# design.net
KiCad netlist of a schematic drawn in Altium Designer
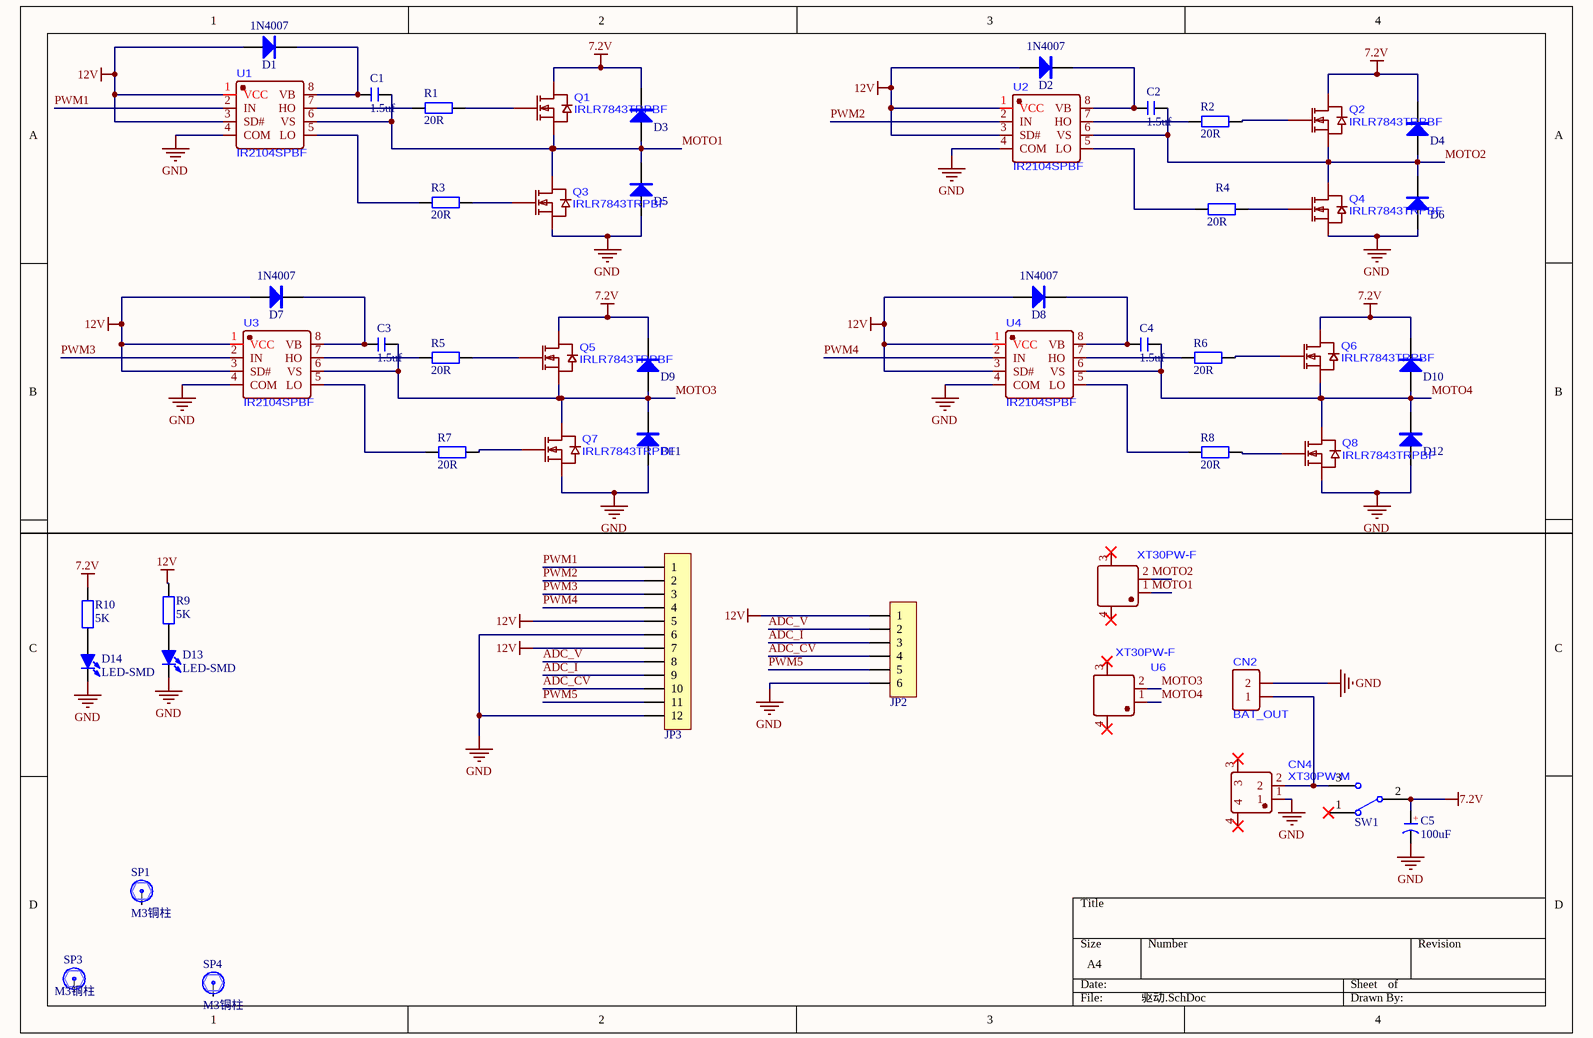
[diagram p0: 驱动.SchDoc]

(export (version "E")
  (design (tool "Eeschema 10.0.6"))
  (components
    (comp (ref "C1")
      (value "1.5uf")
      (footprint "C 0603_M")
      (description "无极性贴片电容")
      (fields (field (name "版权归属") "源创客"))
      (libsource (lib "电阻-电容-电感") (part "C"))
    )
    (comp (ref "C2")
      (value "1.5uf")
      (footprint "C 0603_M")
      (description "无极性贴片电容")
      (fields (field (name "版权归属") "源创客"))
      (libsource (lib "电阻-电容-电感") (part "C"))
    )
    (comp (ref "C3")
      (value "1.5uf")
      (footprint "C 0603_M")
      (description "无极性贴片电容")
      (fields (field (name "版权归属") "源创客"))
      (libsource (lib "电阻-电容-电感") (part "C"))
    )
    (comp (ref "C4")
      (value "1.5uf")
      (footprint "C 0603_M")
      (description "无极性贴片电容")
      (fields (field (name "版权归属") "源创客"))
      (libsource (lib "电阻-电容-电感") (part "C"))
    )
    (comp (ref "C5")
      (value "100uF")
      (footprint "CAP 2.0*5*11-H - BK")
      (description "直插电解电容")
      (fields (field (name "Comment") "C-CAP") (field (name "版权归属") "电协硬件组"))
      (libsource (lib "3.1   - 电阻-电容-电感") (part "C-CAP"))
    )
    (comp (ref "CN2")
      (value "BAT_OUT")
      (footprint "CONN-TH_XT30UPB-F")
      (libsource (lib "驱动") (part "XT30UPB-F"))
    )
    (comp (ref "CN4")
      (value "XT30PW-M")
      (footprint "CONN-TH_XT30PW-M")
      (libsource (lib "主控") (part "XT30PW-M"))
    )
    (comp (ref "D1")
      (value "1N4007")
      (footprint "SMA")
      (description "肖特基二极管")
      (fields (field (name "版权归属") "电协硬件组"))
      (libsource (lib "8.1   - 二极管-整流桥") (part "SS14"))
    )
    (comp (ref "D2")
      (value "1N4007")
      (footprint "SMA")
      (description "肖特基二极管")
      (fields (field (name "版权归属") "电协硬件组"))
      (libsource (lib "8.1   - 二极管-整流桥") (part "SS14"))
    )
    (comp (ref "D3")
      (value "SS14")
      (footprint "SMA")
      (description "肖特基二极管")
      (fields (field (name "版权归属") "电协硬件组"))
      (libsource (lib "8.1   - 二极管-整流桥") (part "SS14"))
    )
    (comp (ref "D4")
      (value "SS14")
      (footprint "SMA")
      (description "肖特基二极管")
      (fields (field (name "版权归属") "电协硬件组"))
      (libsource (lib "8.1   - 二极管-整流桥") (part "SS14"))
    )
    (comp (ref "D5")
      (value "SS14")
      (footprint "SMA")
      (description "肖特基二极管")
      (fields (field (name "版权归属") "电协硬件组"))
      (libsource (lib "8.1   - 二极管-整流桥") (part "SS14"))
    )
    (comp (ref "D6")
      (value "SS14")
      (footprint "SMA")
      (description "肖特基二极管")
      (fields (field (name "版权归属") "电协硬件组"))
      (libsource (lib "8.1   - 二极管-整流桥") (part "SS14"))
    )
    (comp (ref "D7")
      (value "1N4007")
      (footprint "SMA")
      (description "肖特基二极管")
      (fields (field (name "版权归属") "电协硬件组"))
      (libsource (lib "8.1   - 二极管-整流桥") (part "SS14"))
    )
    (comp (ref "D8")
      (value "1N4007")
      (footprint "SMA")
      (description "肖特基二极管")
      (fields (field (name "版权归属") "电协硬件组"))
      (libsource (lib "8.1   - 二极管-整流桥") (part "SS14"))
    )
    (comp (ref "D9")
      (value "SS14")
      (footprint "SMA")
      (description "肖特基二极管")
      (fields (field (name "版权归属") "电协硬件组"))
      (libsource (lib "8.1   - 二极管-整流桥") (part "SS14"))
    )
    (comp (ref "D10")
      (value "SS14")
      (footprint "SMA")
      (description "肖特基二极管")
      (fields (field (name "版权归属") "电协硬件组"))
      (libsource (lib "8.1   - 二极管-整流桥") (part "SS14"))
    )
    (comp (ref "D11")
      (value "SS14")
      (footprint "SMA")
      (description "肖特基二极管")
      (fields (field (name "版权归属") "电协硬件组"))
      (libsource (lib "8.1   - 二极管-整流桥") (part "SS14"))
    )
    (comp (ref "D12")
      (value "SS14")
      (footprint "SMA")
      (description "肖特基二极管")
      (fields (field (name "版权归属") "电协硬件组"))
      (libsource (lib "8.1   - 二极管-整流桥") (part "SS14"))
    )
    (comp (ref "D13")
      (value "LED-SMD")
      (footprint "LED 0603G")
      (description "贴片LED")
      (fields (field (name "版权归属") "电协硬件组"))
      (libsource (lib "9.1   - LED") (part "LED-SMD"))
    )
    (comp (ref "D14")
      (value "LED-SMD")
      (footprint "LED 0603G")
      (description "贴片LED")
      (fields (field (name "版权归属") "电协硬件组"))
      (libsource (lib "9.1   - LED") (part "LED-SMD"))
    )
    (comp (ref "JP2")
      (value "HDR-1X6")
      (footprint "XH2.54-WI-6P")
      (description "6P接插件")
      (fields (field (name "版权归属") "源创客"))
      (libsource (lib "4.5   - 接插件-脚距2.54") (part "Header 6"))
    )
    (comp (ref "JP3")
      (value "HDR-1X12")
      (footprint "XH2.54-WI-12P")
      (description "12P接插件")
      (fields (field (name "版权归属") "源创客"))
      (libsource (lib "4.5   - 接插件-脚距2.54") (part "Header 12"))
    )
    (comp (ref "Q1")
      (value "IRLR7843TRPBF")
      (footprint "TO-252-2_L6.5-W6.1-P4.58-LS10.0-TR")
      (libsource (lib "驱动") (part "IRLR7843TRPBF"))
    )
    (comp (ref "Q2")
      (value "IRLR7843TRPBF")
      (footprint "TO-252-2_L6.5-W6.1-P4.58-LS10.0-TR")
      (libsource (lib "驱动") (part "IRLR7843TRPBF"))
    )
    (comp (ref "Q3")
      (value "IRLR7843TRPBF")
      (footprint "TO-252-2_L6.5-W6.1-P4.58-LS10.0-TR")
      (libsource (lib "驱动") (part "IRLR7843TRPBF"))
    )
    (comp (ref "Q4")
      (value "IRLR7843TRPBF")
      (footprint "TO-252-2_L6.5-W6.1-P4.58-LS10.0-TR")
      (libsource (lib "驱动") (part "IRLR7843TRPBF"))
    )
    (comp (ref "Q5")
      (value "IRLR7843TRPBF")
      (footprint "TO-252-2_L6.5-W6.1-P4.58-LS10.0-TR")
      (libsource (lib "驱动") (part "IRLR7843TRPBF"))
    )
    (comp (ref "Q6")
      (value "IRLR7843TRPBF")
      (footprint "TO-252-2_L6.5-W6.1-P4.58-LS10.0-TR")
      (libsource (lib "驱动") (part "IRLR7843TRPBF"))
    )
    (comp (ref "Q7")
      (value "IRLR7843TRPBF")
      (footprint "TO-252-2_L6.5-W6.1-P4.58-LS10.0-TR")
      (libsource (lib "驱动") (part "IRLR7843TRPBF"))
    )
    (comp (ref "Q8")
      (value "IRLR7843TRPBF")
      (footprint "TO-252-2_L6.5-W6.1-P4.58-LS10.0-TR")
      (libsource (lib "驱动") (part "IRLR7843TRPBF"))
    )
    (comp (ref "R1")
      (value "20R")
      (footprint "C 0603_M")
      (description "贴片电阻")
      (fields (field (name "版权归属") "源创客"))
      (libsource (lib "电阻-电容-电感") (part "R"))
    )
    (comp (ref "R2")
      (value "20R")
      (footprint "C 0603_M")
      (description "贴片电阻")
      (fields (field (name "版权归属") "源创客"))
      (libsource (lib "电阻-电容-电感") (part "R"))
    )
    (comp (ref "R3")
      (value "20R")
      (footprint "C 0603_M")
      (description "贴片电阻")
      (fields (field (name "版权归属") "源创客"))
      (libsource (lib "电阻-电容-电感") (part "R"))
    )
    (comp (ref "R4")
      (value "20R")
      (footprint "C 0603_M")
      (description "贴片电阻")
      (fields (field (name "版权归属") "源创客"))
      (libsource (lib "电阻-电容-电感") (part "R"))
    )
    (comp (ref "R5")
      (value "20R")
      (footprint "C 0603_M")
      (description "贴片电阻")
      (fields (field (name "版权归属") "源创客"))
      (libsource (lib "电阻-电容-电感") (part "R"))
    )
    (comp (ref "R6")
      (value "20R")
      (footprint "C 0603_M")
      (description "贴片电阻")
      (fields (field (name "版权归属") "源创客"))
      (libsource (lib "电阻-电容-电感") (part "R"))
    )
    (comp (ref "R7")
      (value "20R")
      (footprint "C 0603_M")
      (description "贴片电阻")
      (fields (field (name "版权归属") "源创客"))
      (libsource (lib "电阻-电容-电感") (part "R"))
    )
    (comp (ref "R8")
      (value "20R")
      (footprint "C 0603_M")
      (description "贴片电阻")
      (fields (field (name "版权归属") "源创客"))
      (libsource (lib "电阻-电容-电感") (part "R"))
    )
    (comp (ref "R9")
      (value "5K")
      (footprint "R 0603_M")
      (description "贴片电阻")
      (fields (field (name "Comment") "R") (field (name "版权归属") "电协硬件组"))
      (libsource (lib "3.1   - 电阻-电容-电感") (part "R"))
    )
    (comp (ref "R10")
      (value "5K")
      (footprint "R 0603_M")
      (description "贴片电阻")
      (fields (field (name "Comment") "R") (field (name "版权归属") "电协硬件组"))
      (libsource (lib "3.1   - 电阻-电容-电感") (part "R"))
    )
    (comp (ref "SP1")
      (value "M3铜柱")
      (footprint "M3x4+6_L")
      (description "铜柱")
      (fields (field (name "版权归属") "电协硬件组"))
      (libsource (lib "15.1 - 未分类器件") (part "铜柱加头小焊盘"))
    )
    (comp (ref "SP3")
      (value "M3铜柱")
      (footprint "M3x4+6_L")
      (description "铜柱")
      (fields (field (name "版权归属") "电协硬件组"))
      (libsource (lib "15.1 - 未分类器件") (part "铜柱加头小焊盘"))
    )
    (comp (ref "SP4")
      (value "M3铜柱")
      (footprint "M3x4+6_L")
      (description "铜柱")
      (fields (field (name "版权归属") "电协硬件组"))
      (libsource (lib "15.1 - 未分类器件") (part "铜柱加头小焊盘"))
    )
    (comp (ref "SW1")
      (value "MTS-10x")
      (footprint "MTS-10x")
      (description "MTS10x系列3脚扭子开关")
      (fields (field (name "版权归属") "电协硬件组"))
      (libsource (lib "5.1   - 按键-开关") (part "MTS-10x"))
    )
    (comp (ref "U1")
      (value "IR2104SPBF")
      (footprint "SOIC-8_L5.0-W4.0-P1.27-LS6.0-BL")
      (libsource (lib "驱动") (part "IR2104SPBF"))
    )
    (comp (ref "U2")
      (value "IR2104SPBF")
      (footprint "SOIC-8_L5.0-W4.0-P1.27-LS6.0-BL")
      (libsource (lib "驱动") (part "IR2104SPBF"))
    )
    (comp (ref "U3")
      (value "IR2104SPBF")
      (footprint "SOIC-8_L5.0-W4.0-P1.27-LS6.0-BL")
      (libsource (lib "驱动") (part "IR2104SPBF"))
    )
    (comp (ref "U4")
      (value "IR2104SPBF")
      (footprint "SOIC-8_L5.0-W4.0-P1.27-LS6.0-BL")
      (libsource (lib "驱动") (part "IR2104SPBF"))
    )
    (comp (ref "U5")
      (value "XT30PW-F")
      (footprint "CONN-TH_XT30PW-F")
      (libsource (lib "主控") (part "XT30PW-F"))
    )
    (comp (ref "U6")
      (value "XT30PW-F")
      (footprint "CONN-TH_XT30PW-F")
      (libsource (lib "主控") (part "XT30PW-F"))
    )
  )
  (nets
    (net (code "1") (name "/ADC_CV") (class "Default")
      (node (ref "JP2") (pin "4") (pinfunction "4_4") (pintype "passive"))
      (node (ref "JP3") (pin "10") (pinfunction "10_10") (pintype "passive"))
    )
    (net (code "2") (name "/ADC_I") (class "Default")
      (node (ref "JP2") (pin "3") (pinfunction "3_3") (pintype "passive"))
      (node (ref "JP3") (pin "9") (pinfunction "9_9") (pintype "passive"))
    )
    (net (code "3") (name "/ADC_V") (class "Default")
      (node (ref "JP2") (pin "2") (pinfunction "2_2") (pintype "passive"))
      (node (ref "JP3") (pin "8") (pinfunction "8_8") (pintype "passive"))
    )
    (net (code "4") (name "/MOTO1") (class "Default")
      (node (ref "C1") (pin "2") (pinfunction "2_2") (pintype "passive"))
      (node (ref "D3") (pin "1") (pinfunction "A_1") (pintype "passive"))
      (node (ref "D5") (pin "2") (pinfunction "K_2") (pintype "passive"))
      (node (ref "Q1") (pin "3") (pinfunction "S_3") (pintype "passive"))
      (node (ref "Q3") (pin "4") (pinfunction "D_4") (pintype "passive"))
      (node (ref "U1") (pin "6") (pinfunction "VS_6") (pintype "passive"))
      (node (ref "U5") (pin "1") (pinfunction "1_1") (pintype "passive"))
    )
    (net (code "5") (name "/MOTO2") (class "Default")
      (node (ref "C2") (pin "2") (pinfunction "2_2") (pintype "passive"))
      (node (ref "D4") (pin "1") (pinfunction "A_1") (pintype "passive"))
      (node (ref "D6") (pin "2") (pinfunction "K_2") (pintype "passive"))
      (node (ref "Q2") (pin "3") (pinfunction "S_3") (pintype "passive"))
      (node (ref "Q4") (pin "4") (pinfunction "D_4") (pintype "passive"))
      (node (ref "U2") (pin "6") (pinfunction "VS_6") (pintype "passive"))
      (node (ref "U5") (pin "2") (pinfunction "2_2") (pintype "passive"))
    )
    (net (code "6") (name "/MOTO3") (class "Default")
      (node (ref "C3") (pin "2") (pinfunction "2_2") (pintype "passive"))
      (node (ref "D11") (pin "2") (pinfunction "K_2") (pintype "passive"))
      (node (ref "D9") (pin "1") (pinfunction "A_1") (pintype "passive"))
      (node (ref "Q5") (pin "3") (pinfunction "S_3") (pintype "passive"))
      (node (ref "Q7") (pin "4") (pinfunction "D_4") (pintype "passive"))
      (node (ref "U3") (pin "6") (pinfunction "VS_6") (pintype "passive"))
      (node (ref "U6") (pin "2") (pinfunction "2_2") (pintype "passive"))
    )
    (net (code "7") (name "/MOTO4") (class "Default")
      (node (ref "C4") (pin "2") (pinfunction "2_2") (pintype "passive"))
      (node (ref "D10") (pin "1") (pinfunction "A_1") (pintype "passive"))
      (node (ref "D12") (pin "2") (pinfunction "K_2") (pintype "passive"))
      (node (ref "Q6") (pin "3") (pinfunction "S_3") (pintype "passive"))
      (node (ref "Q8") (pin "4") (pinfunction "D_4") (pintype "passive"))
      (node (ref "U4") (pin "6") (pinfunction "VS_6") (pintype "passive"))
      (node (ref "U6") (pin "1") (pinfunction "1_1") (pintype "passive"))
    )
    (net (code "8") (name "/PWM1") (class "Default")
      (node (ref "JP3") (pin "1") (pinfunction "1_1") (pintype "passive"))
      (node (ref "U1") (pin "2") (pinfunction "IN_2") (pintype "passive"))
    )
    (net (code "9") (name "/PWM2") (class "Default")
      (node (ref "JP3") (pin "2") (pinfunction "2_2") (pintype "passive"))
      (node (ref "U2") (pin "2") (pinfunction "IN_2") (pintype "passive"))
    )
    (net (code "10") (name "/PWM3") (class "Default")
      (node (ref "JP3") (pin "3") (pinfunction "3_3") (pintype "passive"))
      (node (ref "U3") (pin "2") (pinfunction "IN_2") (pintype "passive"))
    )
    (net (code "11") (name "/PWM4") (class "Default")
      (node (ref "JP3") (pin "4") (pinfunction "4_4") (pintype "passive"))
      (node (ref "U4") (pin "2") (pinfunction "IN_2") (pintype "passive"))
    )
    (net (code "12") (name "/PWM5") (class "Default")
      (node (ref "JP2") (pin "5") (pinfunction "5_5") (pintype "passive"))
      (node (ref "JP3") (pin "11") (pinfunction "11_11") (pintype "passive"))
    )
    (net (code "13") (name "7.2V") (class "Default")
      (node (ref "C5") (pin "1") (pinfunction "A_1") (pintype "passive"))
      (node (ref "D10") (pin "2") (pinfunction "K_2") (pintype "passive"))
      (node (ref "D3") (pin "2") (pinfunction "K_2") (pintype "passive"))
      (node (ref "D4") (pin "2") (pinfunction "K_2") (pintype "passive"))
      (node (ref "D9") (pin "2") (pinfunction "K_2") (pintype "passive"))
      (node (ref "Q1") (pin "4") (pinfunction "D_4") (pintype "passive"))
      (node (ref "Q2") (pin "4") (pinfunction "D_4") (pintype "passive"))
      (node (ref "Q5") (pin "4") (pinfunction "D_4") (pintype "passive"))
      (node (ref "Q6") (pin "4") (pinfunction "D_4") (pintype "passive"))
      (node (ref "R10") (pin "1") (pinfunction "1_1") (pintype "passive"))
      (node (ref "SW1") (pin "2") (pinfunction "2_2") (pintype "passive"))
    )
    (net (code "14") (name "12V") (class "Default")
      (node (ref "D1") (pin "1") (pinfunction "A_1") (pintype "passive"))
      (node (ref "D2") (pin "1") (pinfunction "A_1") (pintype "passive"))
      (node (ref "D7") (pin "1") (pinfunction "A_1") (pintype "passive"))
      (node (ref "D8") (pin "1") (pinfunction "A_1") (pintype "passive"))
      (node (ref "JP2") (pin "1") (pinfunction "1_1") (pintype "passive"))
      (node (ref "JP3") (pin "5") (pinfunction "5_5") (pintype "passive"))
      (node (ref "JP3") (pin "7") (pinfunction "7_7") (pintype "passive"))
      (node (ref "R9") (pin "1") (pinfunction "1_1") (pintype "passive"))
      (node (ref "U1") (pin "1") (pinfunction "VCC_1") (pintype "passive"))
      (node (ref "U1") (pin "3") (pinfunction "SD#_3") (pintype "passive"))
      (node (ref "U2") (pin "1") (pinfunction "VCC_1") (pintype "passive"))
      (node (ref "U2") (pin "3") (pinfunction "SD#_3") (pintype "passive"))
      (node (ref "U3") (pin "1") (pinfunction "VCC_1") (pintype "passive"))
      (node (ref "U3") (pin "3") (pinfunction "SD#_3") (pintype "passive"))
      (node (ref "U4") (pin "1") (pinfunction "VCC_1") (pintype "passive"))
      (node (ref "U4") (pin "3") (pinfunction "SD#_3") (pintype "passive"))
    )
    (net (code "15") (name "GND") (class "Default")
      (node (ref "C5") (pin "2") (pinfunction "K_2") (pintype "passive"))
      (node (ref "CN2") (pin "2") (pinfunction "2_2") (pintype "passive"))
      (node (ref "CN4") (pin "1") (pinfunction "1_1") (pintype "passive"))
      (node (ref "D11") (pin "1") (pinfunction "A_1") (pintype "passive"))
      (node (ref "D12") (pin "1") (pinfunction "A_1") (pintype "passive"))
      (node (ref "D13") (pin "2") (pinfunction "K_2") (pintype "passive"))
      (node (ref "D14") (pin "2") (pinfunction "K_2") (pintype "passive"))
      (node (ref "D5") (pin "1") (pinfunction "A_1") (pintype "passive"))
      (node (ref "D6") (pin "1") (pinfunction "A_1") (pintype "passive"))
      (node (ref "JP2") (pin "6") (pinfunction "6_6") (pintype "passive"))
      (node (ref "JP3") (pin "12") (pinfunction "12_12") (pintype "passive"))
      (node (ref "JP3") (pin "6") (pinfunction "6_6") (pintype "passive"))
      (node (ref "Q3") (pin "3") (pinfunction "S_3") (pintype "passive"))
      (node (ref "Q4") (pin "3") (pinfunction "S_3") (pintype "passive"))
      (node (ref "Q7") (pin "3") (pinfunction "S_3") (pintype "passive"))
      (node (ref "Q8") (pin "3") (pinfunction "S_3") (pintype "passive"))
      (node (ref "U1") (pin "4") (pinfunction "COM_4") (pintype "passive"))
      (node (ref "U2") (pin "4") (pinfunction "COM_4") (pintype "passive"))
      (node (ref "U3") (pin "4") (pinfunction "COM_4") (pintype "passive"))
      (node (ref "U4") (pin "4") (pinfunction "COM_4") (pintype "passive"))
    )
    (net (code "16") (name "Net-(CN2-Pad1)") (class "Default")
      (node (ref "CN2") (pin "1") (pinfunction "1_1") (pintype "passive"))
      (node (ref "CN4") (pin "2") (pinfunction "2_2") (pintype "passive"))
      (node (ref "SW1") (pin "3") (pinfunction "3_3") (pintype "passive"))
    )
    (net (code "17") (name "Net-(D1-K)") (class "Default")
      (node (ref "C1") (pin "1") (pinfunction "1_1") (pintype "passive"))
      (node (ref "D1") (pin "2") (pinfunction "K_2") (pintype "passive"))
      (node (ref "U1") (pin "8") (pinfunction "VB_8") (pintype "passive"))
    )
    (net (code "18") (name "Net-(D2-K)") (class "Default")
      (node (ref "C2") (pin "1") (pinfunction "1_1") (pintype "passive"))
      (node (ref "D2") (pin "2") (pinfunction "K_2") (pintype "passive"))
      (node (ref "U2") (pin "8") (pinfunction "VB_8") (pintype "passive"))
    )
    (net (code "19") (name "Net-(D7-K)") (class "Default")
      (node (ref "C3") (pin "1") (pinfunction "1_1") (pintype "passive"))
      (node (ref "D7") (pin "2") (pinfunction "K_2") (pintype "passive"))
      (node (ref "U3") (pin "8") (pinfunction "VB_8") (pintype "passive"))
    )
    (net (code "20") (name "Net-(D8-K)") (class "Default")
      (node (ref "C4") (pin "1") (pinfunction "1_1") (pintype "passive"))
      (node (ref "D8") (pin "2") (pinfunction "K_2") (pintype "passive"))
      (node (ref "U4") (pin "8") (pinfunction "VB_8") (pintype "passive"))
    )
    (net (code "21") (name "Net-(D13-A)") (class "Default")
      (node (ref "D13") (pin "1") (pinfunction "A_1") (pintype "passive"))
      (node (ref "R9") (pin "2") (pinfunction "2_2") (pintype "passive"))
    )
    (net (code "22") (name "Net-(D14-A)") (class "Default")
      (node (ref "D14") (pin "1") (pinfunction "A_1") (pintype "passive"))
      (node (ref "R10") (pin "2") (pinfunction "2_2") (pintype "passive"))
    )
    (net (code "23") (name "Net-(Q1-G)") (class "Default")
      (node (ref "Q1") (pin "1") (pinfunction "G_1") (pintype "passive"))
      (node (ref "R1") (pin "2") (pinfunction "2_2") (pintype "passive"))
    )
    (net (code "24") (name "Net-(Q2-G)") (class "Default")
      (node (ref "Q2") (pin "1") (pinfunction "G_1") (pintype "passive"))
      (node (ref "R2") (pin "2") (pinfunction "2_2") (pintype "passive"))
    )
    (net (code "25") (name "Net-(Q3-G)") (class "Default")
      (node (ref "Q3") (pin "1") (pinfunction "G_1") (pintype "passive"))
      (node (ref "R3") (pin "2") (pinfunction "2_2") (pintype "passive"))
    )
    (net (code "26") (name "Net-(Q4-G)") (class "Default")
      (node (ref "Q4") (pin "1") (pinfunction "G_1") (pintype "passive"))
      (node (ref "R4") (pin "2") (pinfunction "2_2") (pintype "passive"))
    )
    (net (code "27") (name "Net-(Q5-G)") (class "Default")
      (node (ref "Q5") (pin "1") (pinfunction "G_1") (pintype "passive"))
      (node (ref "R5") (pin "2") (pinfunction "2_2") (pintype "passive"))
    )
    (net (code "28") (name "Net-(Q6-G)") (class "Default")
      (node (ref "Q6") (pin "1") (pinfunction "G_1") (pintype "passive"))
      (node (ref "R6") (pin "2") (pinfunction "2_2") (pintype "passive"))
    )
    (net (code "29") (name "Net-(Q7-G)") (class "Default")
      (node (ref "Q7") (pin "1") (pinfunction "G_1") (pintype "passive"))
      (node (ref "R7") (pin "2") (pinfunction "2_2") (pintype "passive"))
    )
    (net (code "30") (name "Net-(Q8-G)") (class "Default")
      (node (ref "Q8") (pin "1") (pinfunction "G_1") (pintype "passive"))
      (node (ref "R8") (pin "2") (pinfunction "2_2") (pintype "passive"))
    )
    (net (code "31") (name "Net-(U1-HO)") (class "Default")
      (node (ref "R1") (pin "1") (pinfunction "1_1") (pintype "passive"))
      (node (ref "U1") (pin "7") (pinfunction "HO_7") (pintype "passive"))
    )
    (net (code "32") (name "Net-(U1-LO)") (class "Default")
      (node (ref "R3") (pin "1") (pinfunction "1_1") (pintype "passive"))
      (node (ref "U1") (pin "5") (pinfunction "LO_5") (pintype "passive"))
    )
    (net (code "33") (name "Net-(U2-HO)") (class "Default")
      (node (ref "R2") (pin "1") (pinfunction "1_1") (pintype "passive"))
      (node (ref "U2") (pin "7") (pinfunction "HO_7") (pintype "passive"))
    )
    (net (code "34") (name "Net-(U2-LO)") (class "Default")
      (node (ref "R4") (pin "1") (pinfunction "1_1") (pintype "passive"))
      (node (ref "U2") (pin "5") (pinfunction "LO_5") (pintype "passive"))
    )
    (net (code "35") (name "Net-(U3-HO)") (class "Default")
      (node (ref "R5") (pin "1") (pinfunction "1_1") (pintype "passive"))
      (node (ref "U3") (pin "7") (pinfunction "HO_7") (pintype "passive"))
    )
    (net (code "36") (name "Net-(U3-LO)") (class "Default")
      (node (ref "R7") (pin "1") (pinfunction "1_1") (pintype "passive"))
      (node (ref "U3") (pin "5") (pinfunction "LO_5") (pintype "passive"))
    )
    (net (code "37") (name "Net-(U4-HO)") (class "Default")
      (node (ref "R6") (pin "1") (pinfunction "1_1") (pintype "passive"))
      (node (ref "U4") (pin "7") (pinfunction "HO_7") (pintype "passive"))
    )
    (net (code "38") (name "Net-(U4-LO)") (class "Default")
      (node (ref "R8") (pin "1") (pinfunction "1_1") (pintype "passive"))
      (node (ref "U4") (pin "5") (pinfunction "LO_5") (pintype "passive"))
    )
    (net (code "39") (name "unconnected-(CN4-Pad3)") (class "Default")
      (node (ref "CN4") (pin "3") (pinfunction "3_3") (pintype "passive+no_connect"))
    )
    (net (code "40") (name "unconnected-(CN4-Pad4)") (class "Default")
      (node (ref "CN4") (pin "4") (pinfunction "4_4") (pintype "passive+no_connect"))
    )
    (net (code "41") (name "unconnected-(SP1-Pad1)") (class "Default")
      (node (ref "SP1") (pin "1") (pinfunction "1_1") (pintype "passive"))
    )
    (net (code "42") (name "unconnected-(SP3-Pad1)") (class "Default")
      (node (ref "SP3") (pin "1") (pinfunction "1_1") (pintype "passive"))
    )
    (net (code "43") (name "unconnected-(SP4-Pad1)") (class "Default")
      (node (ref "SP4") (pin "1") (pinfunction "1_1") (pintype "passive"))
    )
    (net (code "44") (name "unconnected-(SW1-Pad1)") (class "Default")
      (node (ref "SW1") (pin "1") (pinfunction "1_1") (pintype "passive+no_connect"))
    )
    (net (code "45") (name "unconnected-(U5-Pad3)") (class "Default")
      (node (ref "U5") (pin "3") (pinfunction "3_3") (pintype "passive+no_connect"))
    )
    (net (code "46") (name "unconnected-(U5-Pad4)") (class "Default")
      (node (ref "U5") (pin "4") (pinfunction "4_4") (pintype "passive+no_connect"))
    )
    (net (code "47") (name "unconnected-(U6-Pad3)") (class "Default")
      (node (ref "U6") (pin "3") (pinfunction "3_3") (pintype "passive+no_connect"))
    )
    (net (code "48") (name "unconnected-(U6-Pad4)") (class "Default")
      (node (ref "U6") (pin "4") (pinfunction "4_4") (pintype "passive+no_connect"))
    )
  )
)
